# CLOCK_GENERATOR.net
KiCad netlist of a schematic drawn in Altium Designer
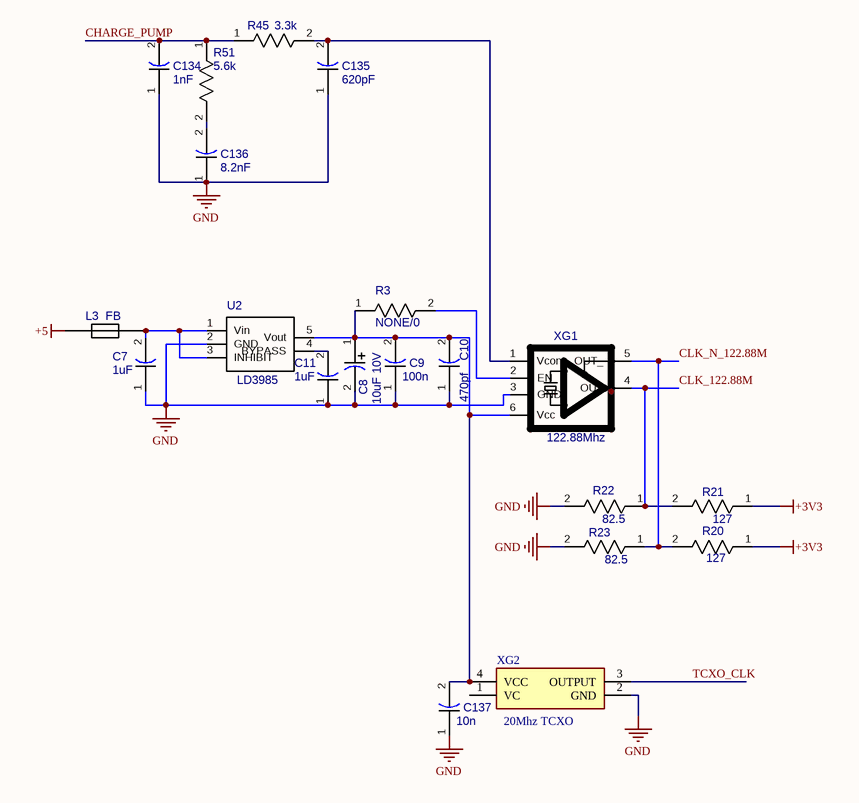
[diagram p0: CLOCK_GENERATOR.SchDoc]

(export (version "E")
  (design (tool "Eeschema 10.0.6"))
  (components
    (comp (ref "C7")
      (value "1uF")
      (footprint "CAP_0805")
      (description "CAP_0805")
      (libsource (lib "*") (part "CAP_0805"))
    )
    (comp (ref "C8")
      (value "10uF 10V")
      (footprint "CAPAE_4.3x4.3h5.4")
      (description "CAPAE_4.3x4.3h5.4")
      (libsource (lib "*") (part "CAPAE_4.3x4.3h5.4"))
    )
    (comp (ref "C9")
      (value "100n")
      (footprint "CAP_0805")
      (description "CAP_0805")
      (libsource (lib "*") (part "CAP_0805"))
    )
    (comp (ref "C10")
      (value "470pf")
      (footprint "CAP_0805")
      (description "CAP_0805")
      (libsource (lib "*") (part "CAP_0805"))
    )
    (comp (ref "C11")
      (value "1uF")
      (footprint "CAP_0805")
      (description "CAP_0805")
      (libsource (lib "*") (part "CAP_0805"))
    )
    (comp (ref "C134")
      (value "1nF")
      (footprint "CAP_0805")
      (description "CAP_0805")
      (libsource (lib "*") (part "CAP_0805"))
    )
    (comp (ref "C135")
      (value "620pF")
      (footprint "CAP_0805")
      (description "CAP_0805")
      (libsource (lib "*") (part "CAP_0805"))
    )
    (comp (ref "C136")
      (value "8.2nF")
      (footprint "CAP_0805")
      (description "CAP_0805")
      (libsource (lib "*") (part "CAP_0805"))
    )
    (comp (ref "C137")
      (value "10n")
      (footprint "CAP_0805")
      (description "CAP_0805")
      (libsource (lib "*") (part "CAP_0805"))
    )
    (comp (ref "L3")
      (value "FB")
      (footprint "IND_FERRITE_BEAD")
      (description "Ferrite bead on conductor")
      (libsource (lib "MOTHERBOARD_1") (part "IND_FERRITE_BEAD"))
    )
    (comp (ref "R3")
      (value "NONE/0")
      (footprint "RES_0805")
      (description "By used crystal")
      (fields (field (name "Comment") "0/NONE"))
      (libsource (lib "*") (part "RES_0805"))
    )
    (comp (ref "R20")
      (value "127")
      (footprint "RES_0805")
      (description "RES_0805")
      (libsource (lib "*") (part "RES_0805"))
    )
    (comp (ref "R21")
      (value "127")
      (footprint "RES_0805")
      (description "RES_0805")
      (libsource (lib "*") (part "RES_0805"))
    )
    (comp (ref "R22")
      (value "82.5")
      (footprint "RES_0805")
      (description "RES_0805")
      (libsource (lib "*") (part "RES_0805"))
    )
    (comp (ref "R23")
      (value "82.5")
      (footprint "RES_0805")
      (description "RES_0805")
      (libsource (lib "*") (part "RES_0805"))
    )
    (comp (ref "R45")
      (value "3.3k")
      (footprint "RES_0805")
      (description "By used crystal")
      (libsource (lib "*") (part "RES_0805"))
    )
    (comp (ref "R51")
      (value "5.6k")
      (footprint "RES_0805")
      (description "By used crystal")
      (libsource (lib "*") (part "RES_0805"))
    )
    (comp (ref "U2") (value "LD3985") (footprint "LD3985") (libsource (lib "*") (part "LD3985")))
    (comp (ref "XG1")
      (value "122.88Mhz")
      (footprint "NV7050SA")
      (description "NV7050SA\r\nVG-4513CA-122.8800M-GGCT3")
      (libsource (lib "*") (part "NV7050SA"))
    )
    (comp (ref "XG2")
      (value "20Mhz TCXO")
      (footprint "SamacSys:581L200X2ITT")
      (description "Crystal or Oscillator")
      (fields
        (field (name "MANUFACTURER_PART_NUMBER") "581L200X2ITT")
        (field (name "MOUSER PART NUMBER") "774-581L200X2ITT")
      )
      (libsource (lib "*") (part "581L200X2ITT"))
    )
  )
  (nets
    (net (code "1") (name "+3V3") (class "Default")
      (node (ref "R20") (pin "1") (pinfunction "1_1") (pintype "passive"))
      (node (ref "R21") (pin "1") (pinfunction "1_1") (pintype "passive"))
    )
    (net (code "2") (name "+5") (class "Default")
      (node (ref "L3") (pin "1") (pinfunction "1_1") (pintype "passive"))
    )
    (net (code "3") (name "/CHARGE_PUMP") (class "Default")
      (node (ref "C134") (pin "2") (pinfunction "2_2") (pintype "passive"))
      (node (ref "R45") (pin "1") (pinfunction "1_1") (pintype "passive"))
      (node (ref "R51") (pin "1") (pinfunction "1_1") (pintype "passive"))
    )
    (net (code "4") (name "/CLK_122.88M") (class "Default")
      (node (ref "R21") (pin "2") (pinfunction "2_2") (pintype "passive"))
      (node (ref "R22") (pin "1") (pinfunction "1_1") (pintype "passive"))
      (node (ref "XG1") (pin "4") (pinfunction "OUT_4") (pintype "passive"))
    )
    (net (code "5") (name "/CLK_N_122.88M") (class "Default")
      (node (ref "R20") (pin "2") (pinfunction "2_2") (pintype "passive"))
      (node (ref "R23") (pin "1") (pinfunction "1_1") (pintype "passive"))
      (node (ref "XG1") (pin "5") (pinfunction "OUT__5") (pintype "passive"))
    )
    (net (code "6") (name "/TCXO_CLK") (class "Default")
      (node (ref "XG2") (pin "3") (pinfunction "OUTPUT_3") (pintype "passive"))
    )
    (net (code "7") (name "GND") (class "Default")
      (node (ref "C10") (pin "1") (pinfunction "1_1") (pintype "passive"))
      (node (ref "C11") (pin "1") (pinfunction "1_1") (pintype "passive"))
      (node (ref "C134") (pin "1") (pinfunction "1_1") (pintype "passive"))
      (node (ref "C135") (pin "1") (pinfunction "1_1") (pintype "passive"))
      (node (ref "C136") (pin "1") (pinfunction "1_1") (pintype "passive"))
      (node (ref "C137") (pin "1") (pinfunction "1_1") (pintype "passive"))
      (node (ref "C7") (pin "1") (pinfunction "1_1") (pintype "passive"))
      (node (ref "C8") (pin "2") (pinfunction "MINUS_2") (pintype "passive"))
      (node (ref "C9") (pin "1") (pinfunction "1_1") (pintype "passive"))
      (node (ref "R22") (pin "2") (pinfunction "2_2") (pintype "passive"))
      (node (ref "R23") (pin "2") (pinfunction "2_2") (pintype "passive"))
      (node (ref "U2") (pin "2") (pinfunction "GND_2") (pintype "passive"))
      (node (ref "XG1") (pin "3") (pinfunction "GND_3") (pintype "passive"))
      (node (ref "XG2") (pin "2") (pinfunction "GND_2") (pintype "passive"))
    )
    (net (code "8") (name "Net-(C8-PLUS)") (class "Default")
      (node (ref "C10") (pin "2") (pinfunction "2_2") (pintype "passive"))
      (node (ref "C137") (pin "2") (pinfunction "2_2") (pintype "passive"))
      (node (ref "C8") (pin "1") (pinfunction "PLUS_1") (pintype "passive"))
      (node (ref "C9") (pin "2") (pinfunction "2_2") (pintype "passive"))
      (node (ref "R3") (pin "1") (pinfunction "1_1") (pintype "passive"))
      (node (ref "U2") (pin "5") (pinfunction "Vout_5") (pintype "passive"))
      (node (ref "XG1") (pin "6") (pinfunction "Vcc_6") (pintype "passive"))
      (node (ref "XG2") (pin "4") (pinfunction "VCC_4") (pintype "passive"))
    )
    (net (code "9") (name "Net-(C136-Pad2)") (class "Default")
      (node (ref "C136") (pin "2") (pinfunction "2_2") (pintype "passive"))
      (node (ref "R51") (pin "2") (pinfunction "2_2") (pintype "passive"))
    )
    (net (code "10") (name "Net-(U2-BYPASS)") (class "Default")
      (node (ref "C11") (pin "2") (pinfunction "2_2") (pintype "passive"))
      (node (ref "U2") (pin "4") (pinfunction "BYPASS_4") (pintype "passive"))
    )
    (net (code "11") (name "Net-(U2-INHIBIT)") (class "Default")
      (node (ref "C7") (pin "2") (pinfunction "2_2") (pintype "passive"))
      (node (ref "L3") (pin "2") (pinfunction "2_2") (pintype "passive"))
      (node (ref "U2") (pin "1") (pinfunction "Vin_1") (pintype "passive"))
      (node (ref "U2") (pin "3") (pinfunction "INHIBIT_3") (pintype "passive"))
    )
    (net (code "12") (name "Net-(XG1-EN)") (class "Default")
      (node (ref "R3") (pin "2") (pinfunction "2_2") (pintype "passive"))
      (node (ref "XG1") (pin "2") (pinfunction "EN_2") (pintype "passive"))
    )
    (net (code "13") (name "Net-(XG1-Vcont)") (class "Default")
      (node (ref "C135") (pin "2") (pinfunction "2_2") (pintype "passive"))
      (node (ref "R45") (pin "2") (pinfunction "2_2") (pintype "passive"))
      (node (ref "XG1") (pin "1") (pinfunction "Vcont_1") (pintype "passive"))
    )
    (net (code "14") (name "unconnected-(XG2-VC-Pad1)") (class "Default")
      (node (ref "XG2") (pin "1") (pinfunction "VC_1") (pintype "passive"))
    )
  )
)
